# pxvi-001.net
KiCad netlist of a schematic drawn in EAGLE
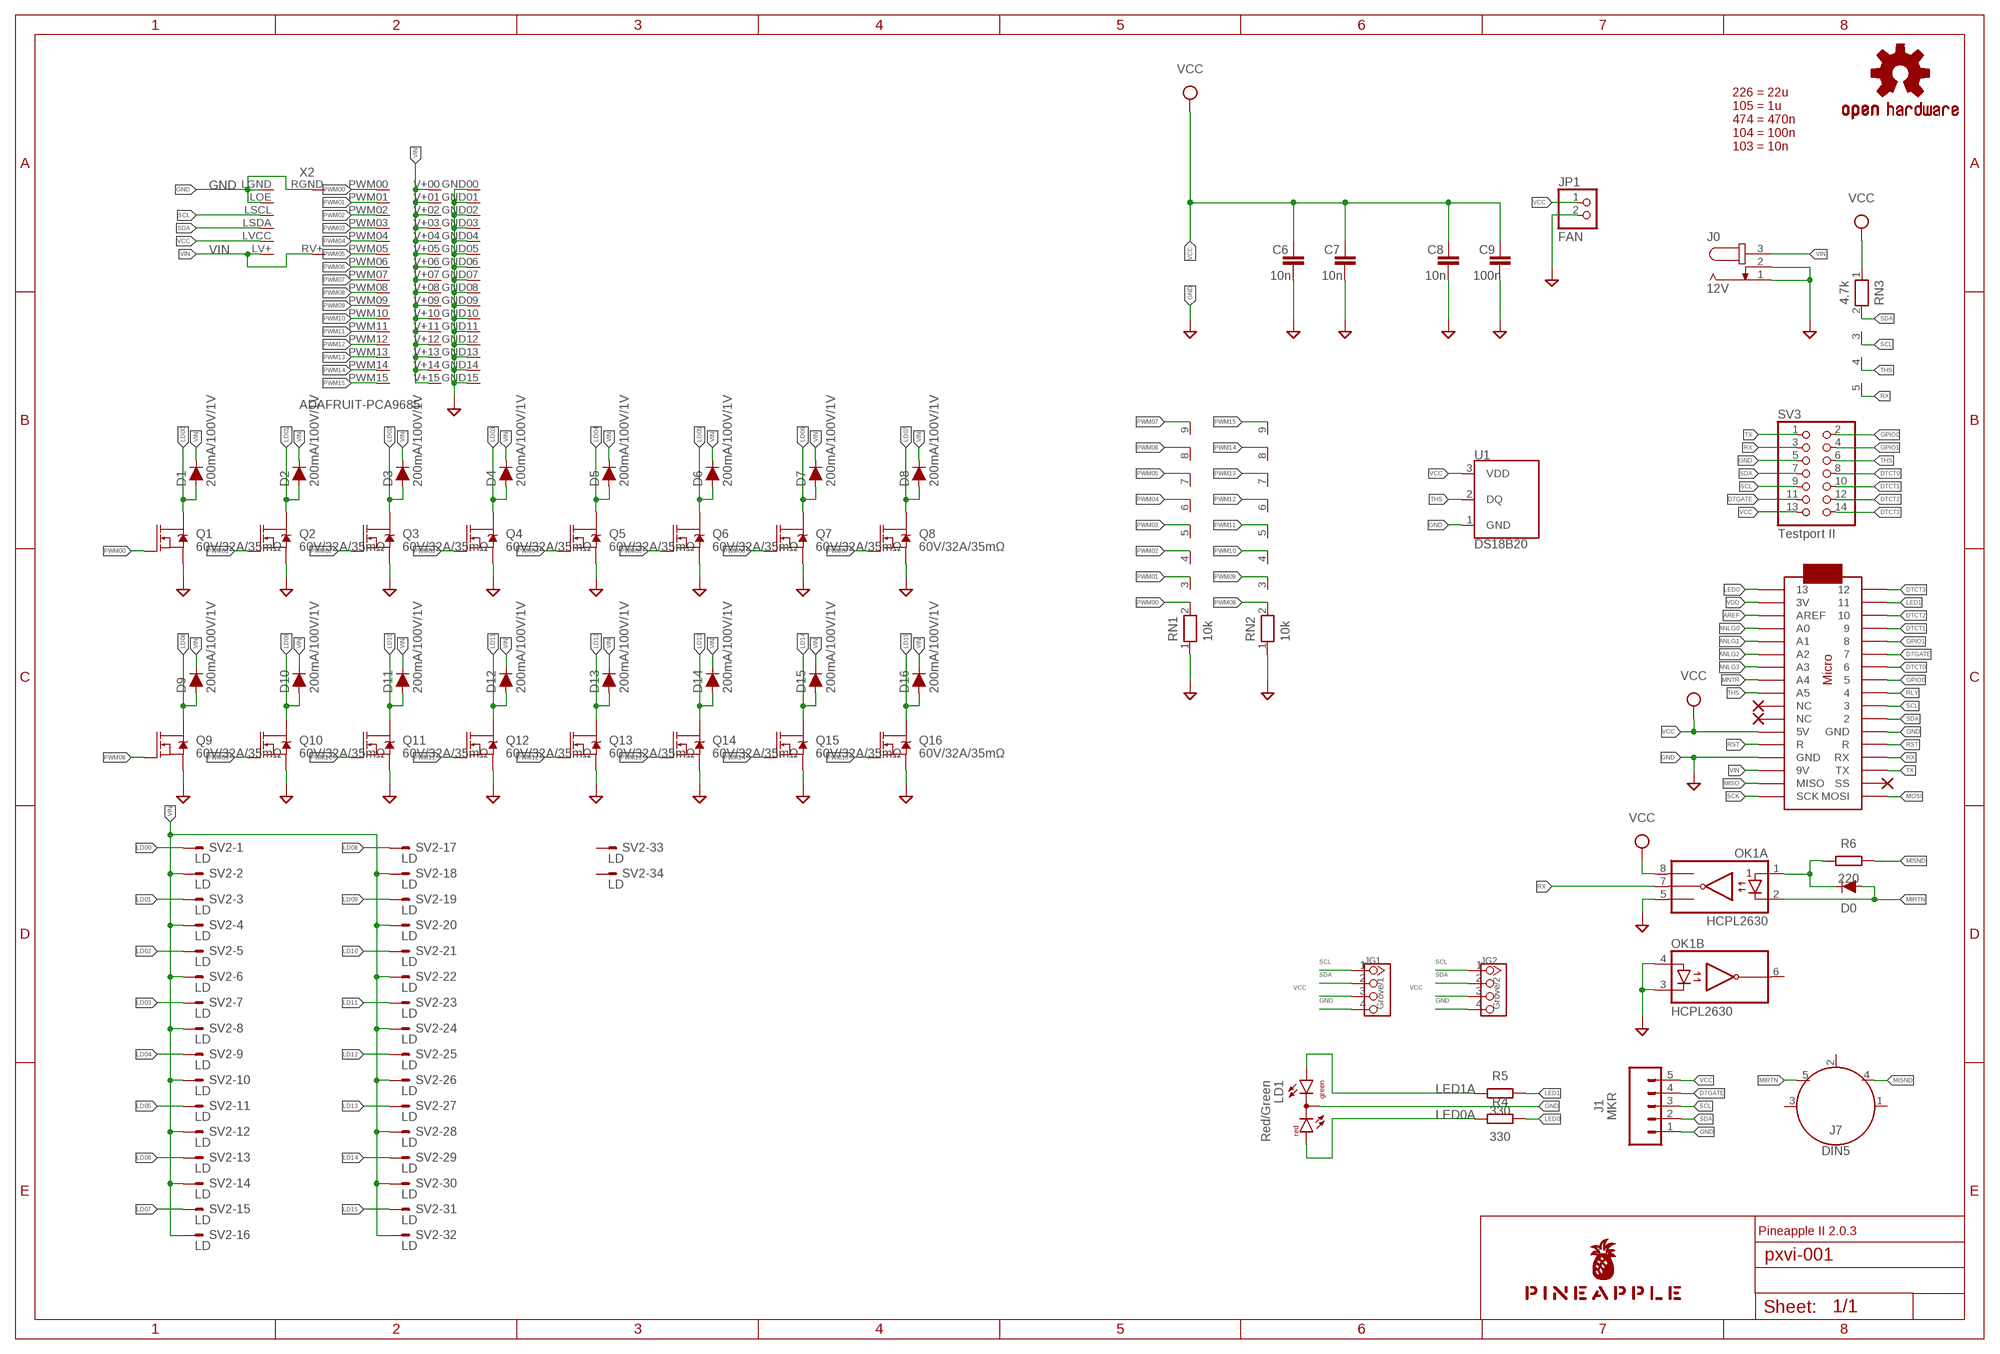
[diagram p0: schematic, sheet 1]

(export (version "E")
  (design (tool "Eeschema 10.0.6"))
  (components
    (comp (ref "C6")
      (value "10n")
      (footprint "eagle-import:C025-024X044")
      (libsource (lib "eagle-import") (part "C-EU025-024X044"))
    )
    (comp (ref "C7")
      (value "10n")
      (footprint "eagle-import:C025-024X044")
      (libsource (lib "eagle-import") (part "C-EU025-024X044"))
    )
    (comp (ref "C8")
      (value "10n")
      (footprint "eagle-import:C025-024X044")
      (libsource (lib "eagle-import") (part "C-EU025-024X044"))
    )
    (comp (ref "C9")
      (value "100n")
      (footprint "eagle-import:C025-024X044")
      (libsource (lib "eagle-import") (part "C-EU025-024X044"))
    )
    (comp (ref "D0")
      (value "DIODE-1N4148")
      (footprint "eagle-import:DIODE-1N4148")
      (libsource (lib "eagle-import") (part "DIODE-1N4148"))
    )
    (comp (ref "D1")
      (value "200mA/100V/1V")
      (footprint "eagle-import:DIODE-1N4148")
      (libsource (lib "eagle-import") (part "DIODE-1N4148"))
    )
    (comp (ref "D2")
      (value "200mA/100V/1V")
      (footprint "eagle-import:DIODE-1N4148")
      (libsource (lib "eagle-import") (part "DIODE-1N4148"))
    )
    (comp (ref "D3")
      (value "200mA/100V/1V")
      (footprint "eagle-import:DIODE-1N4148")
      (libsource (lib "eagle-import") (part "DIODE-1N4148"))
    )
    (comp (ref "D4")
      (value "200mA/100V/1V")
      (footprint "eagle-import:DIODE-1N4148")
      (libsource (lib "eagle-import") (part "DIODE-1N4148"))
    )
    (comp (ref "D5")
      (value "200mA/100V/1V")
      (footprint "eagle-import:DIODE-1N4148")
      (libsource (lib "eagle-import") (part "DIODE-1N4148"))
    )
    (comp (ref "D6")
      (value "200mA/100V/1V")
      (footprint "eagle-import:DIODE-1N4148")
      (libsource (lib "eagle-import") (part "DIODE-1N4148"))
    )
    (comp (ref "D7")
      (value "200mA/100V/1V")
      (footprint "eagle-import:DIODE-1N4148")
      (libsource (lib "eagle-import") (part "DIODE-1N4148"))
    )
    (comp (ref "D8")
      (value "200mA/100V/1V")
      (footprint "eagle-import:DIODE-1N4148")
      (libsource (lib "eagle-import") (part "DIODE-1N4148"))
    )
    (comp (ref "D9")
      (value "200mA/100V/1V")
      (footprint "eagle-import:DIODE-1N4148")
      (libsource (lib "eagle-import") (part "DIODE-1N4148"))
    )
    (comp (ref "D10")
      (value "200mA/100V/1V")
      (footprint "eagle-import:DIODE-1N4148")
      (libsource (lib "eagle-import") (part "DIODE-1N4148"))
    )
    (comp (ref "D11")
      (value "200mA/100V/1V")
      (footprint "eagle-import:DIODE-1N4148")
      (libsource (lib "eagle-import") (part "DIODE-1N4148"))
    )
    (comp (ref "D12")
      (value "200mA/100V/1V")
      (footprint "eagle-import:DIODE-1N4148")
      (libsource (lib "eagle-import") (part "DIODE-1N4148"))
    )
    (comp (ref "D13")
      (value "200mA/100V/1V")
      (footprint "eagle-import:DIODE-1N4148")
      (libsource (lib "eagle-import") (part "DIODE-1N4148"))
    )
    (comp (ref "D14")
      (value "200mA/100V/1V")
      (footprint "eagle-import:DIODE-1N4148")
      (libsource (lib "eagle-import") (part "DIODE-1N4148"))
    )
    (comp (ref "D15")
      (value "200mA/100V/1V")
      (footprint "eagle-import:DIODE-1N4148")
      (libsource (lib "eagle-import") (part "DIODE-1N4148"))
    )
    (comp (ref "D16")
      (value "200mA/100V/1V")
      (footprint "eagle-import:DIODE-1N4148")
      (libsource (lib "eagle-import") (part "DIODE-1N4148"))
    )
    (comp (ref "J0")
      (value "12V")
      (footprint "eagle-import:SPC4077")
      (libsource (lib "eagle-import") (part "JACK-PLUG0"))
    )
    (comp (ref "J1")
      (value "MKR")
      (footprint "eagle-import:JST-5-PTH")
      (libsource (lib "eagle-import") (part "CONN_05JST"))
    )
    (comp (ref "J7")
      (value "DIN5")
      (footprint "eagle-import:DIN5-RA-PTH")
      (libsource (lib "eagle-import") (part "DIN5"))
    )
    (comp (ref "JG1")
      (value "Grove/1")
      (footprint "eagle-import:4P-2.0-90D")
      (libsource (lib "eagle-import") (part "TWIG-4P-2.0'90D'"))
    )
    (comp (ref "JG2")
      (value "Grove/2")
      (footprint "eagle-import:4P-2.0-90D")
      (libsource (lib "eagle-import") (part "TWIG-4P-2.0'90D'"))
    )
    (comp (ref "JP1")
      (value "FAN")
      (footprint "eagle-import:1X02")
      (libsource (lib "eagle-import") (part "PINHD-1X2"))
    )
    (comp (ref "LD1")
      (value "Red/Green")
      (footprint "eagle-import:DUOLED-C-5MM")
      (libsource (lib "eagle-import") (part "DUOLED-RG-C"))
    )
    (comp (ref "LOGO1")
      (value "OSHW-LOGOS-COPPER")
      (footprint "eagle-import:OSHW-LOGO-S_COPPER")
      (libsource (lib "eagle-import") (part "OSHW-LOGOS-COPPER"))
    )
    (comp (ref "MC1")
      (value "ARDUINOMICRO")
      (footprint "eagle-import:ARDUINOMICRO")
      (libsource (lib "eagle-import") (part "ARDUINOMICRO"))
    )
    (comp (ref "OK1")
      (value "HCPL2630")
      (footprint "eagle-import:DIL08")
      (fields (field (name "MF") "AGILENT TECHNOLOGIES") (field (name "MPN") "HCPL-2630-000E"))
      (libsource (lib "eagle-import") (part "HCPL2630"))
    )
    (comp (ref "Q1")
      (value "60V/32A/35mΩ")
      (footprint "eagle-import:TO220V")
      (libsource (lib "eagle-import") (part "MOSFET-NCH-FQP30N06L"))
    )
    (comp (ref "Q2")
      (value "60V/32A/35mΩ")
      (footprint "eagle-import:TO220V")
      (libsource (lib "eagle-import") (part "MOSFET-NCH-FQP30N06L"))
    )
    (comp (ref "Q3")
      (value "60V/32A/35mΩ")
      (footprint "eagle-import:TO220V")
      (libsource (lib "eagle-import") (part "MOSFET-NCH-FQP30N06L"))
    )
    (comp (ref "Q4")
      (value "60V/32A/35mΩ")
      (footprint "eagle-import:TO220V")
      (libsource (lib "eagle-import") (part "MOSFET-NCH-FQP30N06L"))
    )
    (comp (ref "Q5")
      (value "60V/32A/35mΩ")
      (footprint "eagle-import:TO220V")
      (libsource (lib "eagle-import") (part "MOSFET-NCH-FQP30N06L"))
    )
    (comp (ref "Q6")
      (value "60V/32A/35mΩ")
      (footprint "eagle-import:TO220V")
      (libsource (lib "eagle-import") (part "MOSFET-NCH-FQP30N06L"))
    )
    (comp (ref "Q7")
      (value "60V/32A/35mΩ")
      (footprint "eagle-import:TO220V")
      (libsource (lib "eagle-import") (part "MOSFET-NCH-FQP30N06L"))
    )
    (comp (ref "Q8")
      (value "60V/32A/35mΩ")
      (footprint "eagle-import:TO220V")
      (libsource (lib "eagle-import") (part "MOSFET-NCH-FQP30N06L"))
    )
    (comp (ref "Q9")
      (value "60V/32A/35mΩ")
      (footprint "eagle-import:TO220V")
      (libsource (lib "eagle-import") (part "MOSFET-NCH-FQP30N06L"))
    )
    (comp (ref "Q10")
      (value "60V/32A/35mΩ")
      (footprint "eagle-import:TO220V")
      (libsource (lib "eagle-import") (part "MOSFET-NCH-FQP30N06L"))
    )
    (comp (ref "Q11")
      (value "60V/32A/35mΩ")
      (footprint "eagle-import:TO220V")
      (libsource (lib "eagle-import") (part "MOSFET-NCH-FQP30N06L"))
    )
    (comp (ref "Q12")
      (value "60V/32A/35mΩ")
      (footprint "eagle-import:TO220V")
      (libsource (lib "eagle-import") (part "MOSFET-NCH-FQP30N06L"))
    )
    (comp (ref "Q13")
      (value "60V/32A/35mΩ")
      (footprint "eagle-import:TO220V")
      (libsource (lib "eagle-import") (part "MOSFET-NCH-FQP30N06L"))
    )
    (comp (ref "Q14")
      (value "60V/32A/35mΩ")
      (footprint "eagle-import:TO220V")
      (libsource (lib "eagle-import") (part "MOSFET-NCH-FQP30N06L"))
    )
    (comp (ref "Q15")
      (value "60V/32A/35mΩ")
      (footprint "eagle-import:TO220V")
      (libsource (lib "eagle-import") (part "MOSFET-NCH-FQP30N06L"))
    )
    (comp (ref "Q16")
      (value "60V/32A/35mΩ")
      (footprint "eagle-import:TO220V")
      (libsource (lib "eagle-import") (part "MOSFET-NCH-FQP30N06L"))
    )
    (comp (ref "R4")
      (value "330")
      (footprint "eagle-import:0204_5")
      (libsource (lib "eagle-import") (part "R-EU_0204/5"))
    )
    (comp (ref "R5")
      (value "330")
      (footprint "eagle-import:0204_5")
      (libsource (lib "eagle-import") (part "R-EU_0204/5"))
    )
    (comp (ref "R6")
      (value "220")
      (footprint "eagle-import:0204_5")
      (libsource (lib "eagle-import") (part "R-EU_0204/5"))
    )
    (comp (ref "RN1")
      (value "10k")
      (footprint "eagle-import:RN-9")
      (libsource (lib "eagle-import") (part "RN08"))
    )
    (comp (ref "RN2")
      (value "10k")
      (footprint "eagle-import:RN-9")
      (libsource (lib "eagle-import") (part "RN08"))
    )
    (comp (ref "RN3")
      (value "4.7k")
      (footprint "eagle-import:RN-5")
      (libsource (lib "eagle-import") (part "RN04"))
    )
    (comp (ref "SV2")
      (value "LD")
      (footprint "eagle-import:ML34L")
      (libsource (lib "eagle-import") (part "ML34LE"))
    )
    (comp (ref "SV3")
      (value "Testport II")
      (footprint "eagle-import:2X07")
      (libsource (lib "eagle-import") (part "PINHD-2X7"))
    )
    (comp (ref "U$1")
      (value "PINEAPPLE450_SILK")
      (footprint "eagle-import:PINEAPPLE450_SILK")
      (libsource (lib "eagle-import") (part "PINEAPPLE450_SILK"))
    )
    (comp (ref "U1")
      (value "DS18B20")
      (footprint "eagle-import:TO-92-AMMO")
      (libsource (lib "eagle-import") (part "DS18B20"))
    )
    (comp (ref "X2")
      (value "ADAFRUIT-PCA9685")
      (footprint "eagle-import:ADAFRUIT-PCA9685-FOOTPRINT")
      (libsource (lib "eagle-import") (part "ADAFRUIT-PCA9685"))
    )
  )
  (nets
    (net (code "1") (name "/LED0A") (class "Default")
      (node (ref "LD1") (pin "AR") (pinfunction "AR_AR") (pintype "passive"))
      (node (ref "R4") (pin "1") (pinfunction "1_1") (pintype "passive"))
    )
    (net (code "2") (name "/LED1A") (class "Default")
      (node (ref "LD1") (pin "AX") (pinfunction "AG_AX") (pintype "passive"))
      (node (ref "R5") (pin "1") (pinfunction "1_1") (pintype "passive"))
    )
    (net (code "3") (name "ANLG0") (class "Default")
      (node (ref "MC1") (pin "P$31") (pinfunction "A0_P$31") (pintype "bidirectional"))
    )
    (net (code "4") (name "ANLG1") (class "Default")
      (node (ref "MC1") (pin "P$30") (pinfunction "A1_P$30") (pintype "bidirectional"))
    )
    (net (code "5") (name "ANLG2") (class "Default")
      (node (ref "MC1") (pin "P$29") (pinfunction "A2_P$29") (pintype "bidirectional"))
    )
    (net (code "6") (name "ANLG3") (class "Default")
      (node (ref "MC1") (pin "P$28") (pinfunction "A3_P$28") (pintype "bidirectional"))
    )
    (net (code "7") (name "AREF") (class "Default")
      (node (ref "MC1") (pin "P$32") (pinfunction "AREF_P$32") (pintype "bidirectional"))
    )
    (net (code "8") (name "D7GATE") (class "Default")
      (node (ref "J1") (pin "4") (pinfunction "4_4") (pintype "passive"))
      (node (ref "MC1") (pin "P$6") (pinfunction "7_P$6") (pintype "bidirectional"))
      (node (ref "SV3") (pin "11") (pinfunction "11_11") (pintype "passive"))
    )
    (net (code "9") (name "DTCT0") (class "Default")
      (node (ref "MC1") (pin "P$7") (pinfunction "6_P$7") (pintype "bidirectional"))
      (node (ref "SV3") (pin "8") (pinfunction "8_8") (pintype "passive"))
    )
    (net (code "10") (name "DTCT1") (class "Default")
      (node (ref "MC1") (pin "P$4") (pinfunction "9_P$4") (pintype "bidirectional"))
      (node (ref "SV3") (pin "10") (pinfunction "10_10") (pintype "passive"))
    )
    (net (code "11") (name "DTCT2") (class "Default")
      (node (ref "MC1") (pin "P$3") (pinfunction "10_P$3") (pintype "bidirectional"))
      (node (ref "SV3") (pin "12") (pinfunction "12_12") (pintype "passive"))
    )
    (net (code "12") (name "DTCT3") (class "Default")
      (node (ref "MC1") (pin "P$1") (pinfunction "12_P$1") (pintype "bidirectional"))
      (node (ref "SV3") (pin "14") (pinfunction "14_14") (pintype "passive"))
    )
    (net (code "13") (name "GND") (class "Default")
      (node (ref "C6") (pin "2") (pinfunction "2_2") (pintype "passive"))
      (node (ref "C7") (pin "2") (pinfunction "2_2") (pintype "passive"))
      (node (ref "C8") (pin "2") (pinfunction "2_2") (pintype "passive"))
      (node (ref "C9") (pin "2") (pinfunction "2_2") (pintype "passive"))
      (node (ref "J0") (pin "1") (pinfunction "1_1") (pintype "passive"))
      (node (ref "J0") (pin "2") (pinfunction "2_2") (pintype "passive"))
      (node (ref "J1") (pin "1") (pinfunction "1_1") (pintype "passive"))
      (node (ref "JG1") (pin "4") (pinfunction "4_4") (pintype "bidirectional"))
      (node (ref "JG2") (pin "4") (pinfunction "4_4") (pintype "bidirectional"))
      (node (ref "JP1") (pin "2") (pinfunction "2_2") (pintype "passive"))
      (node (ref "LD1") (pin "C") (pinfunction "C_C") (pintype "passive"))
      (node (ref "MC1") (pin "P$12") (pinfunction "GND_P$12") (pintype "bidirectional"))
      (node (ref "MC1") (pin "P$21") (pinfunction "GND_P$21") (pintype "bidirectional"))
      (node (ref "OK1") (pin "3") (pinfunction "C2_3") (pintype "passive"))
      (node (ref "OK1") (pin "4") (pinfunction "A2_4") (pintype "passive"))
      (node (ref "OK1") (pin "5") (pinfunction "GND_5") (pintype "passive"))
      (node (ref "Q1") (pin "3") (pinfunction "S_3") (pintype "bidirectional"))
      (node (ref "Q10") (pin "3") (pinfunction "S_3") (pintype "bidirectional"))
      (node (ref "Q11") (pin "3") (pinfunction "S_3") (pintype "bidirectional"))
      (node (ref "Q12") (pin "3") (pinfunction "S_3") (pintype "bidirectional"))
      (node (ref "Q13") (pin "3") (pinfunction "S_3") (pintype "bidirectional"))
      (node (ref "Q14") (pin "3") (pinfunction "S_3") (pintype "bidirectional"))
      (node (ref "Q15") (pin "3") (pinfunction "S_3") (pintype "bidirectional"))
      (node (ref "Q16") (pin "3") (pinfunction "S_3") (pintype "bidirectional"))
      (node (ref "Q2") (pin "3") (pinfunction "S_3") (pintype "bidirectional"))
      (node (ref "Q3") (pin "3") (pinfunction "S_3") (pintype "bidirectional"))
      (node (ref "Q4") (pin "3") (pinfunction "S_3") (pintype "bidirectional"))
      (node (ref "Q5") (pin "3") (pinfunction "S_3") (pintype "bidirectional"))
      (node (ref "Q6") (pin "3") (pinfunction "S_3") (pintype "bidirectional"))
      (node (ref "Q7") (pin "3") (pinfunction "S_3") (pintype "bidirectional"))
      (node (ref "Q8") (pin "3") (pinfunction "S_3") (pintype "bidirectional"))
      (node (ref "Q9") (pin "3") (pinfunction "S_3") (pintype "bidirectional"))
      (node (ref "RN1") (pin "1") (pinfunction "1_1") (pintype "passive"))
      (node (ref "RN2") (pin "1") (pinfunction "1_1") (pintype "passive"))
      (node (ref "SV3") (pin "5") (pinfunction "5_5") (pintype "passive"))
      (node (ref "U1") (pin "1") (pinfunction "GND_1") (pintype "power_in"))
      (node (ref "X2") (pin "GND00") (pinfunction "45_GND00") (pintype "passive"))
      (node (ref "X2") (pin "GND01") (pinfunction "46_GND01") (pintype "passive"))
      (node (ref "X2") (pin "GND02") (pinfunction "47_GND02") (pintype "passive"))
      (node (ref "X2") (pin "GND03") (pinfunction "48_GND03") (pintype "passive"))
      (node (ref "X2") (pin "GND04") (pinfunction "49_GND04") (pintype "passive"))
      (node (ref "X2") (pin "GND05") (pinfunction "50_GND05") (pintype "passive"))
      (node (ref "X2") (pin "GND06") (pinfunction "51_GND06") (pintype "passive"))
      (node (ref "X2") (pin "GND07") (pinfunction "52_GND07") (pintype "passive"))
      (node (ref "X2") (pin "GND08") (pinfunction "53_GND08") (pintype "passive"))
      (node (ref "X2") (pin "GND09") (pinfunction "54_GND09") (pintype "passive"))
      (node (ref "X2") (pin "GND10") (pinfunction "55_GND10") (pintype "passive"))
      (node (ref "X2") (pin "GND11") (pinfunction "56_GND11") (pintype "passive"))
      (node (ref "X2") (pin "GND12") (pinfunction "57_GND12") (pintype "passive"))
      (node (ref "X2") (pin "GND13") (pinfunction "58_GND13") (pintype "passive"))
      (node (ref "X2") (pin "GND14") (pinfunction "59_GND14") (pintype "passive"))
      (node (ref "X2") (pin "GND15") (pinfunction "60_GND15") (pintype "passive"))
      (node (ref "X2") (pin "LGND") (pinfunction "1_LGND") (pintype "passive"))
      (node (ref "X2") (pin "LOE") (pinfunction "2_LOE") (pintype "passive"))
      (node (ref "X2") (pin "RGND") (pinfunction "7_RGND") (pintype "passive"))
    )
    (net (code "14") (name "GPIO0") (class "Default")
      (node (ref "MC1") (pin "P$8") (pinfunction "5_P$8") (pintype "bidirectional"))
      (node (ref "SV3") (pin "2") (pinfunction "2_2") (pintype "passive"))
    )
    (net (code "15") (name "GPIO1") (class "Default")
      (node (ref "MC1") (pin "P$5") (pinfunction "8_P$5") (pintype "bidirectional"))
      (node (ref "SV3") (pin "4") (pinfunction "4_4") (pintype "passive"))
    )
    (net (code "16") (name "LD00") (class "Default")
      (node (ref "D1") (pin "A") (pinfunction "A_A") (pintype "passive"))
      (node (ref "Q1") (pin "2") (pinfunction "D_2") (pintype "bidirectional"))
      (node (ref "SV2") (pin "1") (pinfunction "S_1") (pintype "passive"))
    )
    (net (code "17") (name "LD01") (class "Default")
      (node (ref "D2") (pin "A") (pinfunction "A_A") (pintype "passive"))
      (node (ref "Q2") (pin "2") (pinfunction "D_2") (pintype "bidirectional"))
      (node (ref "SV2") (pin "3") (pinfunction "S_3") (pintype "passive"))
    )
    (net (code "18") (name "LD02") (class "Default")
      (node (ref "D3") (pin "A") (pinfunction "A_A") (pintype "passive"))
      (node (ref "Q3") (pin "2") (pinfunction "D_2") (pintype "bidirectional"))
      (node (ref "SV2") (pin "5") (pinfunction "S_5") (pintype "passive"))
    )
    (net (code "19") (name "LD03") (class "Default")
      (node (ref "D4") (pin "A") (pinfunction "A_A") (pintype "passive"))
      (node (ref "Q4") (pin "2") (pinfunction "D_2") (pintype "bidirectional"))
      (node (ref "SV2") (pin "7") (pinfunction "S_7") (pintype "passive"))
    )
    (net (code "20") (name "LD04") (class "Default")
      (node (ref "D5") (pin "A") (pinfunction "A_A") (pintype "passive"))
      (node (ref "Q5") (pin "2") (pinfunction "D_2") (pintype "bidirectional"))
      (node (ref "SV2") (pin "9") (pinfunction "S_9") (pintype "passive"))
    )
    (net (code "21") (name "LD05") (class "Default")
      (node (ref "D6") (pin "A") (pinfunction "A_A") (pintype "passive"))
      (node (ref "Q6") (pin "2") (pinfunction "D_2") (pintype "bidirectional"))
      (node (ref "SV2") (pin "11") (pinfunction "S_11") (pintype "passive"))
    )
    (net (code "22") (name "LD06") (class "Default")
      (node (ref "D7") (pin "A") (pinfunction "A_A") (pintype "passive"))
      (node (ref "Q7") (pin "2") (pinfunction "D_2") (pintype "bidirectional"))
      (node (ref "SV2") (pin "13") (pinfunction "S_13") (pintype "passive"))
    )
    (net (code "23") (name "LD07") (class "Default")
      (node (ref "D8") (pin "A") (pinfunction "A_A") (pintype "passive"))
      (node (ref "Q8") (pin "2") (pinfunction "D_2") (pintype "bidirectional"))
      (node (ref "SV2") (pin "15") (pinfunction "S_15") (pintype "passive"))
    )
    (net (code "24") (name "LD08") (class "Default")
      (node (ref "D9") (pin "A") (pinfunction "A_A") (pintype "passive"))
      (node (ref "Q9") (pin "2") (pinfunction "D_2") (pintype "bidirectional"))
      (node (ref "SV2") (pin "17") (pinfunction "S_17") (pintype "passive"))
    )
    (net (code "25") (name "LD09") (class "Default")
      (node (ref "D10") (pin "A") (pinfunction "A_A") (pintype "passive"))
      (node (ref "Q10") (pin "2") (pinfunction "D_2") (pintype "bidirectional"))
      (node (ref "SV2") (pin "19") (pinfunction "S_19") (pintype "passive"))
    )
    (net (code "26") (name "LD10") (class "Default")
      (node (ref "D11") (pin "A") (pinfunction "A_A") (pintype "passive"))
      (node (ref "Q11") (pin "2") (pinfunction "D_2") (pintype "bidirectional"))
      (node (ref "SV2") (pin "21") (pinfunction "S_21") (pintype "passive"))
    )
    (net (code "27") (name "LD11") (class "Default")
      (node (ref "D12") (pin "A") (pinfunction "A_A") (pintype "passive"))
      (node (ref "Q12") (pin "2") (pinfunction "D_2") (pintype "bidirectional"))
      (node (ref "SV2") (pin "23") (pinfunction "S_23") (pintype "passive"))
    )
    (net (code "28") (name "LD12") (class "Default")
      (node (ref "D13") (pin "A") (pinfunction "A_A") (pintype "passive"))
      (node (ref "Q13") (pin "2") (pinfunction "D_2") (pintype "bidirectional"))
      (node (ref "SV2") (pin "25") (pinfunction "S_25") (pintype "passive"))
    )
    (net (code "29") (name "LD13") (class "Default")
      (node (ref "D14") (pin "A") (pinfunction "A_A") (pintype "passive"))
      (node (ref "Q14") (pin "2") (pinfunction "D_2") (pintype "bidirectional"))
      (node (ref "SV2") (pin "27") (pinfunction "S_27") (pintype "passive"))
    )
    (net (code "30") (name "LD14") (class "Default")
      (node (ref "D15") (pin "A") (pinfunction "A_A") (pintype "passive"))
      (node (ref "Q15") (pin "2") (pinfunction "D_2") (pintype "bidirectional"))
      (node (ref "SV2") (pin "29") (pinfunction "S_29") (pintype "passive"))
    )
    (net (code "31") (name "LD15") (class "Default")
      (node (ref "D16") (pin "A") (pinfunction "A_A") (pintype "passive"))
      (node (ref "Q16") (pin "2") (pinfunction "D_2") (pintype "bidirectional"))
      (node (ref "SV2") (pin "31") (pinfunction "S_31") (pintype "passive"))
    )
    (net (code "32") (name "LED0") (class "Default")
      (node (ref "MC1") (pin "P$34") (pinfunction "13_P$34") (pintype "bidirectional"))
      (node (ref "R4") (pin "2") (pinfunction "2_2") (pintype "passive"))
    )
    (net (code "33") (name "LED1") (class "Default")
      (node (ref "MC1") (pin "P$2") (pinfunction "11_P$2") (pintype "bidirectional"))
      (node (ref "R5") (pin "2") (pinfunction "2_2") (pintype "passive"))
    )
    (net (code "34") (name "MIRTN") (class "Default")
      (node (ref "D0") (pin "A") (pinfunction "A_A") (pintype "passive"))
      (node (ref "J7") (pin "5") (pinfunction "5_5") (pintype "bidirectional"))
      (node (ref "OK1") (pin "2") (pinfunction "C1_2") (pintype "passive"))
    )
    (net (code "35") (name "MISND") (class "Default")
      (node (ref "J7") (pin "4") (pinfunction "4_4") (pintype "bidirectional"))
      (node (ref "R6") (pin "2") (pinfunction "2_2") (pintype "passive"))
    )
    (net (code "36") (name "MISO") (class "Default")
      (node (ref "MC1") (pin "P$19") (pinfunction "MISO_P$19") (pintype "bidirectional"))
    )
    (net (code "37") (name "MNTR") (class "Default")
      (node (ref "MC1") (pin "P$27") (pinfunction "A4_P$27") (pintype "bidirectional"))
    )
    (net (code "38") (name "MOSI") (class "Default")
      (node (ref "MC1") (pin "P$17") (pinfunction "MOSI_P$17") (pintype "bidirectional"))
    )
    (net (code "39") (name "Net-(OK1A-A1)") (class "Default")
      (node (ref "D0") (pin "C") (pinfunction "C_C") (pintype "passive"))
      (node (ref "OK1") (pin "1") (pinfunction "A1_1") (pintype "passive"))
      (node (ref "R6") (pin "1") (pinfunction "1_1") (pintype "passive"))
    )
    (net (code "40") (name "PWM00") (class "Default")
      (node (ref "Q1") (pin "1") (pinfunction "G_1") (pintype "bidirectional"))
      (node (ref "RN1") (pin "2") (pinfunction "2_2") (pintype "passive"))
      (node (ref "X2") (pin "PWM00") (pinfunction "13_PWM00") (pintype "passive"))
    )
    (net (code "41") (name "PWM01") (class "Default")
      (node (ref "Q2") (pin "1") (pinfunction "G_1") (pintype "bidirectional"))
      (node (ref "RN1") (pin "3") (pinfunction "3_3") (pintype "passive"))
      (node (ref "X2") (pin "PWM01") (pinfunction "14_PWM01") (pintype "passive"))
    )
    (net (code "42") (name "PWM02") (class "Default")
      (node (ref "Q3") (pin "1") (pinfunction "G_1") (pintype "bidirectional"))
      (node (ref "RN1") (pin "4") (pinfunction "4_4") (pintype "passive"))
      (node (ref "X2") (pin "PWM02") (pinfunction "15_PWM02") (pintype "passive"))
    )
    (net (code "43") (name "PWM03") (class "Default")
      (node (ref "Q4") (pin "1") (pinfunction "G_1") (pintype "bidirectional"))
      (node (ref "RN1") (pin "5") (pinfunction "5_5") (pintype "passive"))
      (node (ref "X2") (pin "PWM03") (pinfunction "16_PWM03") (pintype "passive"))
    )
    (net (code "44") (name "PWM04") (class "Default")
      (node (ref "Q5") (pin "1") (pinfunction "G_1") (pintype "bidirectional"))
      (node (ref "RN1") (pin "6") (pinfunction "6_6") (pintype "passive"))
      (node (ref "X2") (pin "PWM04") (pinfunction "17_PWM04") (pintype "passive"))
    )
    (net (code "45") (name "PWM05") (class "Default")
      (node (ref "Q6") (pin "1") (pinfunction "G_1") (pintype "bidirectional"))
      (node (ref "RN1") (pin "7") (pinfunction "7_7") (pintype "passive"))
      (node (ref "X2") (pin "PWM05") (pinfunction "18_PWM05") (pintype "passive"))
    )
    (net (code "46") (name "PWM06") (class "Default")
      (node (ref "Q7") (pin "1") (pinfunction "G_1") (pintype "bidirectional"))
      (node (ref "RN1") (pin "8") (pinfunction "8_8") (pintype "passive"))
      (node (ref "X2") (pin "PWM06") (pinfunction "19_PWM06") (pintype "passive"))
    )
    (net (code "47") (name "PWM07") (class "Default")
      (node (ref "Q8") (pin "1") (pinfunction "G_1") (pintype "bidirectional"))
      (node (ref "RN1") (pin "9") (pinfunction "9_9") (pintype "passive"))
      (node (ref "X2") (pin "PWM07") (pinfunction "20_PWM07") (pintype "passive"))
    )
    (net (code "48") (name "PWM08") (class "Default")
      (node (ref "Q9") (pin "1") (pinfunction "G_1") (pintype "bidirectional"))
      (node (ref "RN2") (pin "2") (pinfunction "2_2") (pintype "passive"))
      (node (ref "X2") (pin "PWM08") (pinfunction "21_PWM08") (pintype "passive"))
    )
    (net (code "49") (name "PWM09") (class "Default")
      (node (ref "Q10") (pin "1") (pinfunction "G_1") (pintype "bidirectional"))
      (node (ref "RN2") (pin "3") (pinfunction "3_3") (pintype "passive"))
      (node (ref "X2") (pin "PWM09") (pinfunction "22_PWM09") (pintype "passive"))
    )
    (net (code "50") (name "PWM10") (class "Default")
      (node (ref "Q11") (pin "1") (pinfunction "G_1") (pintype "bidirectional"))
      (node (ref "RN2") (pin "4") (pinfunction "4_4") (pintype "passive"))
      (node (ref "X2") (pin "PWM10") (pinfunction "23_PWM10") (pintype "passive"))
    )
    (net (code "51") (name "PWM11") (class "Default")
      (node (ref "Q12") (pin "1") (pinfunction "G_1") (pintype "bidirectional"))
      (node (ref "RN2") (pin "5") (pinfunction "5_5") (pintype "passive"))
      (node (ref "X2") (pin "PWM11") (pinfunction "24_PWM11") (pintype "passive"))
    )
    (net (code "52") (name "PWM12") (class "Default")
      (node (ref "Q13") (pin "1") (pinfunction "G_1") (pintype "bidirectional"))
      (node (ref "RN2") (pin "6") (pinfunction "6_6") (pintype "passive"))
      (node (ref "X2") (pin "PWM12") (pinfunction "25_PWM12") (pintype "passive"))
    )
    (net (code "53") (name "PWM13") (class "Default")
      (node (ref "Q14") (pin "1") (pinfunction "G_1") (pintype "bidirectional"))
      (node (ref "RN2") (pin "7") (pinfunction "7_7") (pintype "passive"))
      (node (ref "X2") (pin "PWM13") (pinfunction "26_PWM13") (pintype "passive"))
    )
    (net (code "54") (name "PWM14") (class "Default")
      (node (ref "Q15") (pin "1") (pinfunction "G_1") (pintype "bidirectional"))
      (node (ref "RN2") (pin "8") (pinfunction "8_8") (pintype "passive"))
      (node (ref "X2") (pin "PWM14") (pinfunction "27_PWM14") (pintype "passive"))
    )
    (net (code "55") (name "PWM15") (class "Default")
      (node (ref "Q16") (pin "1") (pinfunction "G_1") (pintype "bidirectional"))
      (node (ref "RN2") (pin "9") (pinfunction "9_9") (pintype "passive"))
      (node (ref "X2") (pin "PWM15") (pinfunction "28_PWM15") (pintype "passive"))
    )
    (net (code "56") (name "RLY") (class "Default")
      (node (ref "MC1") (pin "P$9") (pinfunction "4_P$9") (pintype "bidirectional"))
    )
    (net (code "57") (name "RST") (class "Default")
      (node (ref "MC1") (pin "P$13") (pinfunction "R_P$13") (pintype "bidirectional"))
      (node (ref "MC1") (pin "P$22") (pinfunction "R_P$22") (pintype "bidirectional"))
    )
    (net (code "58") (name "RX") (class "Default")
      (node (ref "MC1") (pin "P$14") (pinfunction "RX_P$14") (pintype "bidirectional"))
      (node (ref "OK1") (pin "7") (pinfunction "VO1_7") (pintype "passive"))
      (node (ref "RN3") (pin "5") (pinfunction "5_5") (pintype "passive"))
      (node (ref "SV3") (pin "3") (pinfunction "3_3") (pintype "passive"))
    )
    (net (code "59") (name "SCK") (class "Default")
      (node (ref "MC1") (pin "P$18") (pinfunction "SCK_P$18") (pintype "bidirectional"))
    )
    (net (code "60") (name "SCL") (class "Default")
      (node (ref "J1") (pin "3") (pinfunction "3_3") (pintype "passive"))
      (node (ref "JG1") (pin "1") (pinfunction "1_1") (pintype "bidirectional"))
      (node (ref "JG2") (pin "1") (pinfunction "1_1") (pintype "bidirectional"))
      (node (ref "MC1") (pin "P$10") (pinfunction "3_P$10") (pintype "bidirectional"))
      (node (ref "RN3") (pin "3") (pinfunction "3_3") (pintype "passive"))
      (node (ref "SV3") (pin "9") (pinfunction "9_9") (pintype "passive"))
      (node (ref "X2") (pin "LSCL") (pinfunction "3_LSCL") (pintype "passive"))
    )
    (net (code "61") (name "SDA") (class "Default")
      (node (ref "J1") (pin "2") (pinfunction "2_2") (pintype "passive"))
      (node (ref "JG1") (pin "2") (pinfunction "2_2") (pintype "bidirectional"))
      (node (ref "JG2") (pin "2") (pinfunction "2_2") (pintype "bidirectional"))
      (node (ref "MC1") (pin "P$11") (pinfunction "2_P$11") (pintype "bidirectional"))
      (node (ref "RN3") (pin "2") (pinfunction "2_2") (pintype "passive"))
      (node (ref "SV3") (pin "7") (pinfunction "7_7") (pintype "passive"))
      (node (ref "X2") (pin "LSDA") (pinfunction "4_LSDA") (pintype "passive"))
    )
    (net (code "62") (name "THS") (class "Default")
      (node (ref "MC1") (pin "P$26") (pinfunction "A5_P$26") (pintype "bidirectional"))
      (node (ref "RN3") (pin "4") (pinfunction "4_4") (pintype "passive"))
      (node (ref "SV3") (pin "6") (pinfunction "6_6") (pintype "passive"))
      (node (ref "U1") (pin "2") (pinfunction "DQ_2") (pintype "bidirectional"))
    )
    (net (code "63") (name "TX") (class "Default")
      (node (ref "MC1") (pin "P$15") (pinfunction "TX_P$15") (pintype "bidirectional"))
      (node (ref "SV3") (pin "1") (pinfunction "1_1") (pintype "passive"))
    )
    (net (code "64") (name "VCC") (class "Default")
      (node (ref "C6") (pin "1") (pinfunction "1_1") (pintype "passive"))
      (node (ref "C7") (pin "1") (pinfunction "1_1") (pintype "passive"))
      (node (ref "C8") (pin "1") (pinfunction "1_1") (pintype "passive"))
      (node (ref "C9") (pin "1") (pinfunction "1_1") (pintype "passive"))
      (node (ref "J1") (pin "5") (pinfunction "5_5") (pintype "passive"))
      (node (ref "JG1") (pin "3") (pinfunction "3_3") (pintype "bidirectional"))
      (node (ref "JG2") (pin "3") (pinfunction "3_3") (pintype "bidirectional"))
      (node (ref "JP1") (pin "1") (pinfunction "1_1") (pintype "passive"))
      (node (ref "MC1") (pin "P$23") (pinfunction "5V_P$23") (pintype "bidirectional"))
      (node (ref "OK1") (pin "8") (pinfunction "VCC_8") (pintype "passive"))
      (node (ref "RN3") (pin "1") (pinfunction "1_1") (pintype "passive"))
      (node (ref "SV3") (pin "13") (pinfunction "13_13") (pintype "passive"))
      (node (ref "U1") (pin "3") (pinfunction "VDD_3") (pintype "power_in"))
      (node (ref "X2") (pin "LVCC") (pinfunction "5_LVCC") (pintype "passive"))
    )
    (net (code "65") (name "VDD") (class "Default")
      (node (ref "MC1") (pin "P$33") (pinfunction "3V_P$33") (pintype "bidirectional"))
    )
    (net (code "66") (name "VIN") (class "Default")
      (node (ref "D1") (pin "C") (pinfunction "C_C") (pintype "passive"))
      (node (ref "D10") (pin "C") (pinfunction "C_C") (pintype "passive"))
      (node (ref "D11") (pin "C") (pinfunction "C_C") (pintype "passive"))
      (node (ref "D12") (pin "C") (pinfunction "C_C") (pintype "passive"))
      (node (ref "D13") (pin "C") (pinfunction "C_C") (pintype "passive"))
      (node (ref "D14") (pin "C") (pinfunction "C_C") (pintype "passive"))
      (node (ref "D15") (pin "C") (pinfunction "C_C") (pintype "passive"))
      (node (ref "D16") (pin "C") (pinfunction "C_C") (pintype "passive"))
      (node (ref "D2") (pin "C") (pinfunction "C_C") (pintype "passive"))
      (node (ref "D3") (pin "C") (pinfunction "C_C") (pintype "passive"))
      (node (ref "D4") (pin "C") (pinfunction "C_C") (pintype "passive"))
      (node (ref "D5") (pin "C") (pinfunction "C_C") (pintype "passive"))
      (node (ref "D6") (pin "C") (pinfunction "C_C") (pintype "passive"))
      (node (ref "D7") (pin "C") (pinfunction "C_C") (pintype "passive"))
      (node (ref "D8") (pin "C") (pinfunction "C_C") (pintype "passive"))
      (node (ref "D9") (pin "C") (pinfunction "C_C") (pintype "passive"))
      (node (ref "J0") (pin "3") (pinfunction "3_3") (pintype "passive"))
      (node (ref "MC1") (pin "P$20") (pinfunction "9V_P$20") (pintype "bidirectional"))
      (node (ref "SV2") (pin "10") (pinfunction "S_10") (pintype "passive"))
      (node (ref "SV2") (pin "12") (pinfunction "S_12") (pintype "passive"))
      (node (ref "SV2") (pin "14") (pinfunction "S_14") (pintype "passive"))
      (node (ref "SV2") (pin "16") (pinfunction "S_16") (pintype "passive"))
      (node (ref "SV2") (pin "18") (pinfunction "S_18") (pintype "passive"))
      (node (ref "SV2") (pin "2") (pinfunction "S_2") (pintype "passive"))
      (node (ref "SV2") (pin "20") (pinfunction "S_20") (pintype "passive"))
      (node (ref "SV2") (pin "22") (pinfunction "S_22") (pintype "passive"))
      (node (ref "SV2") (pin "24") (pinfunction "S_24") (pintype "passive"))
      (node (ref "SV2") (pin "26") (pinfunction "S_26") (pintype "passive"))
      (node (ref "SV2") (pin "28") (pinfunction "S_28") (pintype "passive"))
      (node (ref "SV2") (pin "30") (pinfunction "S_30") (pintype "passive"))
      (node (ref "SV2") (pin "32") (pinfunction "S_32") (pintype "passive"))
      (node (ref "SV2") (pin "4") (pinfunction "S_4") (pintype "passive"))
      (node (ref "SV2") (pin "6") (pinfunction "S_6") (pintype "passive"))
      (node (ref "SV2") (pin "8") (pinfunction "S_8") (pintype "passive"))
      (node (ref "X2") (pin "LV+") (pinfunction "6_LV+") (pintype "passive"))
      (node (ref "X2") (pin "RV+") (pinfunction "12_RV+") (pintype "passive"))
      (node (ref "X2") (pin "V+00") (pinfunction "29_V+00") (pintype "passive"))
      (node (ref "X2") (pin "V+01") (pinfunction "30_V+01") (pintype "passive"))
      (node (ref "X2") (pin "V+02") (pinfunction "31_V+02") (pintype "passive"))
      (node (ref "X2") (pin "V+03") (pinfunction "32_V+03") (pintype "passive"))
      (node (ref "X2") (pin "V+04") (pinfunction "33_V+04") (pintype "passive"))
      (node (ref "X2") (pin "V+05") (pinfunction "34_V+05") (pintype "passive"))
      (node (ref "X2") (pin "V+06") (pinfunction "35_V+06") (pintype "passive"))
      (node (ref "X2") (pin "V+07") (pinfunction "36_V+07") (pintype "passive"))
      (node (ref "X2") (pin "V+08") (pinfunction "37_V+08") (pintype "passive"))
      (node (ref "X2") (pin "V+09") (pinfunction "38_V+09") (pintype "passive"))
      (node (ref "X2") (pin "V+10") (pinfunction "39_V+10") (pintype "passive"))
      (node (ref "X2") (pin "V+11") (pinfunction "40_V+11") (pintype "passive"))
      (node (ref "X2") (pin "V+12") (pinfunction "41_V+12") (pintype "passive"))
      (node (ref "X2") (pin "V+13") (pinfunction "42_V+13") (pintype "passive"))
      (node (ref "X2") (pin "V+14") (pinfunction "43_V+14") (pintype "passive"))
      (node (ref "X2") (pin "V+15") (pinfunction "44_V+15") (pintype "passive"))
    )
    (net (code "67") (name "unconnected-(J7-Pad1)") (class "Default")
      (node (ref "J7") (pin "1") (pinfunction "1_1") (pintype "bidirectional"))
    )
    (net (code "68") (name "unconnected-(J7-Pad2)") (class "Default")
      (node (ref "J7") (pin "2") (pinfunction "2_2") (pintype "bidirectional"))
    )
    (net (code "69") (name "unconnected-(J7-Pad3)") (class "Default")
      (node (ref "J7") (pin "3") (pinfunction "3_3") (pintype "bidirectional"))
    )
    (net (code "70") (name "unconnected-(MC1-NC-PadP$24)") (class "Default")
      (node (ref "MC1") (pin "P$24") (pinfunction "NC_P$24") (pintype "bidirectional"))
    )
    (net (code "71") (name "unconnected-(MC1-NC-PadP$25)") (class "Default")
      (node (ref "MC1") (pin "P$25") (pinfunction "NC_P$25") (pintype "bidirectional"))
    )
    (net (code "72") (name "unconnected-(MC1-SS-PadP$16)") (class "Default")
      (node (ref "MC1") (pin "P$16") (pinfunction "SS_P$16") (pintype "bidirectional"))
    )
    (net (code "73") (name "unconnected-(OK1B-VO2-Pad6)") (class "Default")
      (node (ref "OK1") (pin "6") (pinfunction "VO2_6") (pintype "passive"))
    )
    (net (code "74") (name "unconnected-(SV2AA-S-Pad33)") (class "Default")
      (node (ref "SV2") (pin "33") (pinfunction "S_33") (pintype "passive"))
    )
    (net (code "75") (name "unconnected-(SV2AB-S-Pad34)") (class "Default")
      (node (ref "SV2") (pin "34") (pinfunction "S_34") (pintype "passive"))
    )
  )
)
